# technologies.net
KiCad netlist of a schematic drawn in EAGLE
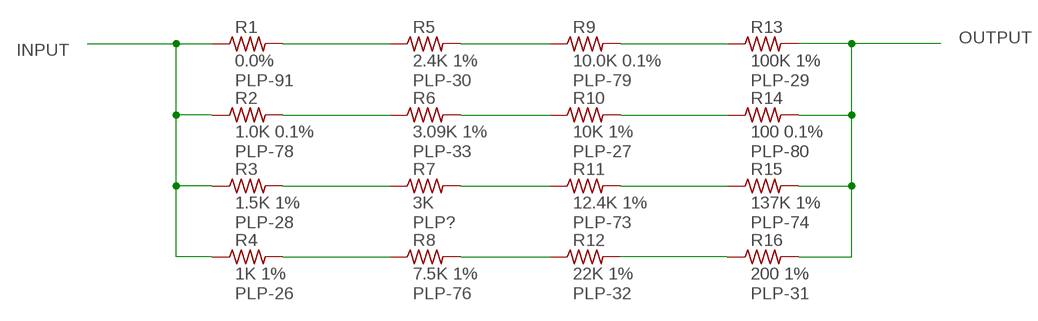
[diagram p0: schematic, sheet 1]

(export (version "E")
  (design (tool "Eeschema 10.0.6"))
  (components
    (comp (ref "R1")
      (value "0.0%")
      (footprint "eagle-import:DISCRETE_R0603")
      (libsource (lib "eagle-import") (part "RES-6030.0OHM"))
    )
    (comp (ref "R2")
      (value "1.0K 0.1%")
      (footprint "eagle-import:DISCRETE_R0603")
      (libsource (lib "eagle-import") (part "RES-6031.0K0.1%"))
    )
    (comp (ref "R3")
      (value "1.5K 1%")
      (footprint "eagle-import:DISCRETE_R0603")
      (libsource (lib "eagle-import") (part "RES-6031.5K1%"))
    )
    (comp (ref "R4")
      (value "1K 1%")
      (footprint "eagle-import:DISCRETE_R0603")
      (libsource (lib "eagle-import") (part "RES-6031K1%"))
    )
    (comp (ref "R5")
      (value "2.4K 1%")
      (footprint "eagle-import:DISCRETE_R0603")
      (libsource (lib "eagle-import") (part "RES-6032.4K1%"))
    )
    (comp (ref "R6")
      (value "3.09K 1%")
      (footprint "eagle-import:DISCRETE_R0603")
      (libsource (lib "eagle-import") (part "RES-6033.09K1%"))
    )
    (comp (ref "R7")
      (value "3K")
      (footprint "eagle-import:DISCRETE_R0603")
      (libsource (lib "eagle-import") (part "RES-6033K5%"))
    )
    (comp (ref "R8")
      (value "7.5K 1%")
      (footprint "eagle-import:DISCRETE_R0603")
      (libsource (lib "eagle-import") (part "RES-6037.5K1%"))
    )
    (comp (ref "R9")
      (value "10.0K 0.1%")
      (footprint "eagle-import:DISCRETE_R0603")
      (libsource (lib "eagle-import") (part "RES-60310.0K0.1%"))
    )
    (comp (ref "R10")
      (value "10K 1%")
      (footprint "eagle-import:DISCRETE_R0603")
      (libsource (lib "eagle-import") (part "RES-60310K1%"))
    )
    (comp (ref "R11")
      (value "12.4K 1%")
      (footprint "eagle-import:DISCRETE_R0603")
      (libsource (lib "eagle-import") (part "RES-60312.4K1%"))
    )
    (comp (ref "R12")
      (value "22K 1%")
      (footprint "eagle-import:DISCRETE_R0603")
      (libsource (lib "eagle-import") (part "RES-60322K1%"))
    )
    (comp (ref "R13")
      (value "100K 1%")
      (footprint "eagle-import:DISCRETE_R0603")
      (libsource (lib "eagle-import") (part "RES-603100K1%"))
    )
    (comp (ref "R14")
      (value "100 0.1%")
      (footprint "eagle-import:DISCRETE_R0603")
      (libsource (lib "eagle-import") (part "RES-603100OHM0.1%"))
    )
    (comp (ref "R15")
      (value "137K 1%")
      (footprint "eagle-import:DISCRETE_R0603")
      (libsource (lib "eagle-import") (part "RES-603137K1%"))
    )
    (comp (ref "R16")
      (value "200 1%")
      (footprint "eagle-import:DISCRETE_R0603")
      (libsource (lib "eagle-import") (part "RES-603200OHM1%"))
    )
  )
  (nets
    (net (code "1") (name "/INPUT") (class "Default")
      (node (ref "R1") (pin "1") (pinfunction "1_1") (pintype "passive"))
      (node (ref "R2") (pin "1") (pinfunction "1_1") (pintype "passive"))
      (node (ref "R3") (pin "1") (pinfunction "1_1") (pintype "passive"))
      (node (ref "R4") (pin "1") (pinfunction "1_1") (pintype "passive"))
    )
    (net (code "2") (name "/OUTPUT") (class "Default")
      (node (ref "R13") (pin "2") (pinfunction "2_2") (pintype "passive"))
      (node (ref "R14") (pin "2") (pinfunction "2_2") (pintype "passive"))
      (node (ref "R15") (pin "2") (pinfunction "2_2") (pintype "passive"))
      (node (ref "R16") (pin "2") (pinfunction "2_2") (pintype "passive"))
    )
    (net (code "3") (name "Net-(R1-Pad2)") (class "Default")
      (node (ref "R1") (pin "2") (pinfunction "2_2") (pintype "passive"))
      (node (ref "R5") (pin "1") (pinfunction "1_1") (pintype "passive"))
    )
    (net (code "4") (name "Net-(R2-Pad2)") (class "Default")
      (node (ref "R2") (pin "2") (pinfunction "2_2") (pintype "passive"))
      (node (ref "R6") (pin "1") (pinfunction "1_1") (pintype "passive"))
    )
    (net (code "5") (name "Net-(R3-Pad2)") (class "Default")
      (node (ref "R3") (pin "2") (pinfunction "2_2") (pintype "passive"))
      (node (ref "R7") (pin "1") (pinfunction "1_1") (pintype "passive"))
    )
    (net (code "6") (name "Net-(R4-Pad2)") (class "Default")
      (node (ref "R4") (pin "2") (pinfunction "2_2") (pintype "passive"))
      (node (ref "R8") (pin "1") (pinfunction "1_1") (pintype "passive"))
    )
    (net (code "7") (name "Net-(R5-Pad2)") (class "Default")
      (node (ref "R5") (pin "2") (pinfunction "2_2") (pintype "passive"))
      (node (ref "R9") (pin "1") (pinfunction "1_1") (pintype "passive"))
    )
    (net (code "8") (name "Net-(R10-Pad1)") (class "Default")
      (node (ref "R10") (pin "1") (pinfunction "1_1") (pintype "passive"))
      (node (ref "R6") (pin "2") (pinfunction "2_2") (pintype "passive"))
    )
    (net (code "9") (name "Net-(R10-Pad2)") (class "Default")
      (node (ref "R10") (pin "2") (pinfunction "2_2") (pintype "passive"))
      (node (ref "R14") (pin "1") (pinfunction "1_1") (pintype "passive"))
    )
    (net (code "10") (name "Net-(R11-Pad1)") (class "Default")
      (node (ref "R11") (pin "1") (pinfunction "1_1") (pintype "passive"))
      (node (ref "R7") (pin "2") (pinfunction "2_2") (pintype "passive"))
    )
    (net (code "11") (name "Net-(R11-Pad2)") (class "Default")
      (node (ref "R11") (pin "2") (pinfunction "2_2") (pintype "passive"))
      (node (ref "R15") (pin "1") (pinfunction "1_1") (pintype "passive"))
    )
    (net (code "12") (name "Net-(R12-Pad1)") (class "Default")
      (node (ref "R12") (pin "1") (pinfunction "1_1") (pintype "passive"))
      (node (ref "R8") (pin "2") (pinfunction "2_2") (pintype "passive"))
    )
    (net (code "13") (name "Net-(R12-Pad2)") (class "Default")
      (node (ref "R12") (pin "2") (pinfunction "2_2") (pintype "passive"))
      (node (ref "R16") (pin "1") (pinfunction "1_1") (pintype "passive"))
    )
    (net (code "14") (name "Net-(R13-Pad1)") (class "Default")
      (node (ref "R13") (pin "1") (pinfunction "1_1") (pintype "passive"))
      (node (ref "R9") (pin "2") (pinfunction "2_2") (pintype "passive"))
    )
  )
)
